# Power.net
KiCad netlist of a schematic drawn in Altium Designer
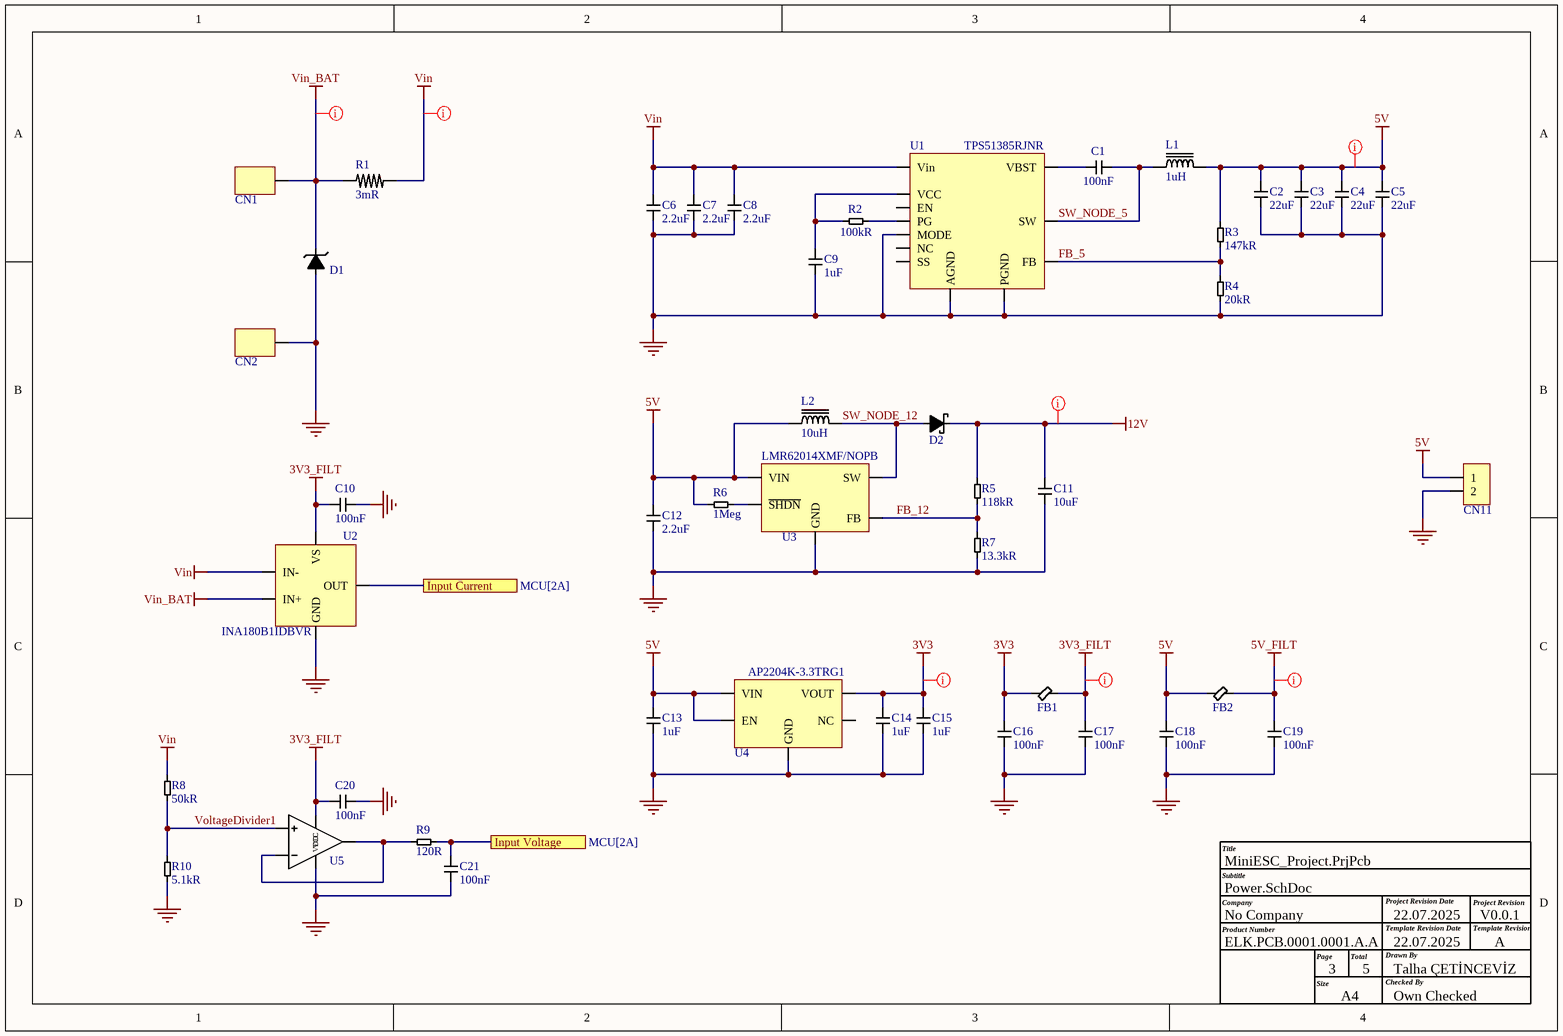
[diagram p0: Power.SchDoc]

(export (version "E")
  (design (tool "Eeschema 10.0.6"))
  (components
    (comp (ref "C1")
      (value "100nF")
      (footprint "CAP 0805")
      (description "50V 100nF X7R ±10% 0805 Multilayer Ceramic Capacitors MLCC - SMD/SMT ROHS")
      (fields
        (field (name "MANUFACTURER") "Samsung")
        (field (name "MANUFACTURER PART NUMBER") "CL21B104KBCNNNC")
      )
      (libsource (lib "ESC_Int") (part "CL21B104KBCNNNC"))
    )
    (comp (ref "C2")
      (value "22uF")
      (footprint "CAP 1206")
      (description "Multilayer Ceramic Capacitor, 22 uF, 10 V, ± 10%, X7R, 1206 [3216 Metric]")
      (fields
        (field (name "MANUFACTURER") "Samsung")
        (field (name "MANUFACTURER PART NUMBER") "CL31B226KPHNNNE")
      )
      (libsource (lib "ESC_Int") (part "CL31B226KPHNNNE"))
    )
    (comp (ref "C3")
      (value "22uF")
      (footprint "CAP 1206")
      (description "Multilayer Ceramic Capacitor, 22 uF, 10 V, ± 10%, X7R, 1206 [3216 Metric]")
      (fields
        (field (name "MANUFACTURER") "Samsung")
        (field (name "MANUFACTURER PART NUMBER") "CL31B226KPHNNNE")
      )
      (libsource (lib "ESC_Int") (part "CL31B226KPHNNNE"))
    )
    (comp (ref "C4")
      (value "22uF")
      (footprint "CAP 1206")
      (description "Multilayer Ceramic Capacitor, 22 uF, 10 V, ± 10%, X7R, 1206 [3216 Metric]")
      (fields
        (field (name "MANUFACTURER") "Samsung")
        (field (name "MANUFACTURER PART NUMBER") "CL31B226KPHNNNE")
      )
      (libsource (lib "ESC_Int") (part "CL31B226KPHNNNE"))
    )
    (comp (ref "C5")
      (value "22uF")
      (footprint "CAP 1206")
      (description "Multilayer Ceramic Capacitor, 22 uF, 10 V, ± 10%, X7R, 1206 [3216 Metric]")
      (fields
        (field (name "MANUFACTURER") "Samsung")
        (field (name "MANUFACTURER PART NUMBER") "CL31B226KPHNNNE")
      )
      (libsource (lib "ESC_Int") (part "CL31B226KPHNNNE"))
    )
    (comp (ref "C6")
      (value "2.2uF")
      (footprint "CAP 1206")
      (description "50V 2.2uF X7R ±10% 1206 Multilayer Ceramic Capacitors MLCC - SMD/SMT ROHS")
      (fields
        (field (name "MANUFACTURER") "Samsung")
        (field (name "MANUFACTURER PART NUMBER") "CL31B225KBHNNNE")
      )
      (libsource (lib "ESC_Int") (part "CL31B225KBHNNNE"))
    )
    (comp (ref "C7")
      (value "2.2uF")
      (footprint "CAP 1206")
      (description "50V 2.2uF X7R ±10% 1206 Multilayer Ceramic Capacitors MLCC - SMD/SMT ROHS")
      (fields
        (field (name "MANUFACTURER") "Samsung")
        (field (name "MANUFACTURER PART NUMBER") "CL31B225KBHNNNE")
      )
      (libsource (lib "ESC_Int") (part "CL31B225KBHNNNE"))
    )
    (comp (ref "C8")
      (value "2.2uF")
      (footprint "CAP 1206")
      (description "50V 2.2uF X7R ±10% 1206 Multilayer Ceramic Capacitors MLCC - SMD/SMT ROHS")
      (fields
        (field (name "MANUFACTURER") "Samsung")
        (field (name "MANUFACTURER PART NUMBER") "CL31B225KBHNNNE")
      )
      (libsource (lib "ESC_Int") (part "CL31B225KBHNNNE"))
    )
    (comp (ref "C9")
      (value "1uF")
      (footprint "CAP 0805")
      (description "Ceramic Capacitor, Ceramic, 50V, 10% +Tol, 10% -Tol, X7R, 15% TC, 1uF, Surface Mount, 0805")
      (fields
        (field (name "MANUFACTURER") "Yageo")
        (field (name "MANUFACTURER PART NUMBER") "CC0805KKX7R9BB105")
      )
      (libsource (lib "ESC_Int") (part "CC0805KKX7R9BB105"))
    )
    (comp (ref "C10")
      (value "100nF")
      (footprint "CAP 0603")
      (description "Multilayer Ceramic Capacitor, CC Series, 0.1 - F, - 10%, X7R, 50 V, 0603 [1608 Metric]")
      (fields
        (field (name "MANUFACTURER") "Yageo")
        (field (name "MANUFACTURER PART NUMBER") "CC0603KRX7R9BB104")
      )
      (libsource (lib "ESC_Int") (part "CC0603KRX7R9BB104"))
    )
    (comp (ref "C11")
      (value "10uF")
      (footprint "CAP 0805")
      (description "25V 10uF X5R ±10% 0805 Multilayer Ceramic Capacitors MLCC - SMD/SMT ROHS")
      (fields
        (field (name "MANUFACTURER") "Samsung")
        (field (name "MANUFACTURER PART NUMBER") "CL21A106KAYNNNE")
      )
      (libsource (lib "ESC_Int") (part "CL21A106KAYNNNE"))
    )
    (comp (ref "C12")
      (value "2.2uF")
      (footprint "CAP 1206")
      (description "50V 2.2uF X7R ±10% 1206 Multilayer Ceramic Capacitors MLCC - SMD/SMT ROHS")
      (fields
        (field (name "MANUFACTURER") "Samsung")
        (field (name "MANUFACTURER PART NUMBER") "CL31B225KBHNNNE")
      )
      (libsource (lib "ESC_Int") (part "CL31B225KBHNNNE"))
    )
    (comp (ref "C13")
      (value "1uF")
      (footprint "CAP 1206")
      (description "Cap Ceramic 1uF 16V X7R 10% SMD 1206 125°C Embossed T/R")
      (fields
        (field (name "MANUFACTURER") "Samsung")
        (field (name "MANUFACTURER PART NUMBER") "CL31B105KOFNNNE")
      )
      (libsource (lib "ESC_Int") (part "CL31B105KOFNNNE"))
    )
    (comp (ref "C14")
      (value "1uF")
      (footprint "CAP 1206")
      (description "Cap Ceramic 1uF 16V X7R 10% SMD 1206 125°C Embossed T/R")
      (fields
        (field (name "MANUFACTURER") "Samsung")
        (field (name "MANUFACTURER PART NUMBER") "CL31B105KOFNNNE")
      )
      (libsource (lib "ESC_Int") (part "CL31B105KOFNNNE"))
    )
    (comp (ref "C15")
      (value "1uF")
      (footprint "CAP 1206")
      (description "Cap Ceramic 1uF 16V X7R 10% SMD 1206 125°C Embossed T/R")
      (fields
        (field (name "MANUFACTURER") "Samsung")
        (field (name "MANUFACTURER PART NUMBER") "CL31B105KOFNNNE")
      )
      (libsource (lib "ESC_Int") (part "CL31B105KOFNNNE"))
    )
    (comp (ref "C16")
      (value "100nF")
      (footprint "CAP 0603")
      (description "Multilayer Ceramic Capacitor, CC Series, 0.1 - F, - 10%, X7R, 50 V, 0603 [1608 Metric]")
      (fields
        (field (name "MANUFACTURER") "Yageo")
        (field (name "MANUFACTURER PART NUMBER") "CC0603KRX7R9BB104")
      )
      (libsource (lib "ESC_Int") (part "CC0603KRX7R9BB104"))
    )
    (comp (ref "C17")
      (value "100nF")
      (footprint "CAP 0603")
      (description "Multilayer Ceramic Capacitor, CC Series, 0.1 - F, - 10%, X7R, 50 V, 0603 [1608 Metric]")
      (fields
        (field (name "MANUFACTURER") "Yageo")
        (field (name "MANUFACTURER PART NUMBER") "CC0603KRX7R9BB104")
      )
      (libsource (lib "ESC_Int") (part "CC0603KRX7R9BB104"))
    )
    (comp (ref "C18")
      (value "100nF")
      (footprint "CAP 0603")
      (description "Multilayer Ceramic Capacitor, CC Series, 0.1 - F, - 10%, X7R, 50 V, 0603 [1608 Metric]")
      (fields
        (field (name "MANUFACTURER") "Yageo")
        (field (name "MANUFACTURER PART NUMBER") "CC0603KRX7R9BB104")
      )
      (libsource (lib "ESC_Int") (part "CC0603KRX7R9BB104"))
    )
    (comp (ref "C19")
      (value "100nF")
      (footprint "CAP 0603")
      (description "Multilayer Ceramic Capacitor, CC Series, 0.1 - F, - 10%, X7R, 50 V, 0603 [1608 Metric]")
      (fields
        (field (name "MANUFACTURER") "Yageo")
        (field (name "MANUFACTURER PART NUMBER") "CC0603KRX7R9BB104")
      )
      (libsource (lib "ESC_Int") (part "CC0603KRX7R9BB104"))
    )
    (comp (ref "C20")
      (value "100nF")
      (footprint "CAP 0603")
      (description "Multilayer Ceramic Capacitor, CC Series, 0.1 - F, - 10%, X7R, 50 V, 0603 [1608 Metric]")
      (fields
        (field (name "MANUFACTURER") "Yageo")
        (field (name "MANUFACTURER PART NUMBER") "CC0603KRX7R9BB104")
      )
      (libsource (lib "ESC_Int") (part "CC0603KRX7R9BB104"))
    )
    (comp (ref "C21")
      (value "100nF")
      (footprint "CAP 0603")
      (description "Multilayer Ceramic Capacitor, CC Series, 0.1 - F, - 10%, X7R, 50 V, 0603 [1608 Metric]")
      (fields
        (field (name "MANUFACTURER") "Yageo")
        (field (name "MANUFACTURER PART NUMBER") "CC0603KRX7R9BB104")
      )
      (libsource (lib "ESC_Int") (part "CC0603KRX7R9BB104"))
    )
    (comp (ref "CN1")
      (value "SMD PAD 1")
      (footprint "SMD PAD 1")
      (libsource (lib "ESC_Int") (part "SMD PAD 1"))
    )
    (comp (ref "CN2")
      (value "SMD PAD 1")
      (footprint "SMD PAD 1")
      (libsource (lib "ESC_Int") (part "SMD PAD 1"))
    )
    (comp (ref "CN11")
      (value "2 Pin SMD")
      (footprint "2 Pin SMD")
      (libsource (lib "ESC_Int") (part "2 Pin SMD"))
    )
    (comp (ref "D1")
      (value "SMAJ33CA-HT")
      (footprint "SMA")
      (description "DIODE TVS 400W 33V DO214AC SMA")
      (fields
        (field (name "MANUFACTURER") "Taiwan Semiconductor")
        (field (name "MANUFACTURER PART NUMBER") "SMAJ33CAH")
      )
      (libsource (lib "ESC_Int") (part "SMAJ33CA-HT"))
    )
    (comp (ref "D2")
      (value "SL02-GS08")
      (footprint "DO-219AB")
      (description "Rectifier Diode Schottky 20V 1.1A 10ns Automotive 2-Pin SMF T/R")
      (fields (field (name "MANUFACTURER") "Vishay"))
      (libsource (lib "ESC_Int") (part "SL02-GS08"))
    )
    (comp (ref "FB1")
      (value "BLM18EG601SN1D")
      (footprint "FB 0603")
      (description "Ferrite Beads Multi-Layer 600Ohm 25% 100MHz 500mA 350mOhm DCR 0603 Paper T/R")
      (fields (field (name "MANUFACTURER") "Murata") (field (name "TOLERANCE") "25%"))
      (libsource (lib "ESC_Int") (part "BLM18EG601SN1D"))
    )
    (comp (ref "FB2")
      (value "BLM18EG601SN1D")
      (footprint "FB 0603")
      (description "Ferrite Beads Multi-Layer 600Ohm 25% 100MHz 500mA 350mOhm DCR 0603 Paper T/R")
      (fields (field (name "MANUFACTURER") "Murata") (field (name "TOLERANCE") "25%"))
      (libsource (lib "ESC_Int") (part "BLM18EG601SN1D"))
    )
    (comp (ref "L1")
      (value "1uH")
      (footprint "11x10")
      (description "1 µH Shielded Molded Inductor 18 A 3.3mOhm Max Nonstandard")
      (fields
        (field (name "MANUFACTURER") "Laird")
        (field (name "MANUFACTURER PART NUMBER") "MGAH10041R0M-10")
      )
      (libsource (lib "ESC_Int") (part "MGAH10041R0M-10"))
    )
    (comp (ref "L2")
      (value "10uH")
      (footprint "3.9x3.9")
      (description "Power inductor, shielded, 20/30% tol, SMT, RoHS, lead-free, halogen-free")
      (fields
        (field (name "MANUFACTURER") "Coilcraft")
        (field (name "MANUFACTURER PART NUMBER") "LPS4018-103MRC")
      )
      (libsource (lib "ESC_Int") (part "LPS4018-103MRC"))
    )
    (comp (ref "R1")
      (value "3mR")
      (footprint "3920")
      (description "RES.SHUNT 3920 3m Ohms 1% 5W AUTO ALUCHROM SMT")
      (fields
        (field (name "MANUFACTURER") "Isabellenhütte")
        (field (name "MANUFACTURER PART NUMBER") "BVS-A-R003-1.0")
      )
      (libsource (lib "ESC_Int") (part "BVS-A-R003-1.0"))
    )
    (comp (ref "R2")
      (value "100kR")
      (footprint "RES 0603")
      (description "100Mw Thick Film Resistors 100Ppm/ 1% 100K 0603 Chip Resistor Surface Mount Rohs")
      (fields
        (field (name "MANUFACTURER") "Yageo")
        (field (name "MANUFACTURER PART NUMBER") "RC0603FR-07100KL")
      )
      (libsource (lib "ESC_Int") (part "RC0603FR-07100KL"))
    )
    (comp (ref "R3")
      (value "147kR")
      (footprint "RES 0603")
      (description "RES.(1608) 0603 147K Ohms 1% 1/10W-S 100PPM")
      (fields
        (field (name "MANUFACTURER") "Multicomp")
        (field (name "MANUFACTURER PART NUMBER") "MC0603SAF1473T5E")
      )
      (libsource (lib "ESC_Int") (part "0603SAF1473T5E"))
    )
    (comp (ref "R4")
      (value "20kR")
      (footprint "RES 0603")
      (description "RES.(1608) 0603 20K Ohms 1% 1/10W-S 100PPM")
      (fields
        (field (name "MANUFACTURER") "Royal Electronic Factory")
        (field (name "MANUFACTURER PART NUMBER") "0603SAF2002T5E")
      )
      (libsource (lib "ESC_Int") (part "0603SAF2002T5E"))
    )
    (comp (ref "R5")
      (value "118kR")
      (footprint "RES 0603")
      (description "Resistor, Thick Film, 118 Kohm, 100MW, 1%")
      (fields
        (field (name "MANUFACTURER") "Multicomp")
        (field (name "MANUFACTURER PART NUMBER") "MC0603SAF1183T5E")
      )
      (libsource (lib "ESC_Int") (part "0603SAF1183T5E"))
    )
    (comp (ref "R6")
      (value "1Meg")
      (footprint "RES 0603")
      (description "Res Thick Film 0603 1M Ohm 5% 0.1W(1/10W) ±200ppm/°C Pad SMD T/R")
      (fields
        (field (name "MANUFACTURER") "Royal Electronic Factory")
        (field (name "MANUFACTURER PART NUMBER") "0603SAJ0105T5E")
      )
      (libsource (lib "ESC_Int") (part "0603SAJ0105T5E"))
    )
    (comp (ref "R7")
      (value "13.3kR")
      (footprint "RES 0603")
      (description "SMD Chip Resistor, 13.3 kohm, ï¿½ 1%, 100 mW, 0603 [1608 Metric], Thick Film, General Purpose")
      (fields
        (field (name "MANUFACTURER") "Yageo")
        (field (name "MANUFACTURER PART NUMBER") "RC0603FR-0713K3L")
      )
      (libsource (lib "ESC_Int") (part "RC0603FR-0713K3L"))
    )
    (comp (ref "R8")
      (value "50kR")
      (footprint "RES 0805")
      (description "RES.(2012) 0805 50K Ohms 1% 1/8W-S 100PPM")
      (fields
        (field (name "MANUFACTURER") "ROYALOHM")
        (field (name "MANUFACTURER PART NUMBER") "0805S8F5002T5E")
      )
      (libsource (lib "ESC_Int") (part "0805S8F5002T5E"))
    )
    (comp (ref "R9")
      (value "120R")
      (footprint "RES 0603")
      (description "RES.(1608) 0603 120 Ohms 1% 1/10W-S 100PPM")
      (fields
        (field (name "MANUFACTURER") "ROYALOHM")
        (field (name "MANUFACTURER PART NUMBER") "0603SAF1200T5E")
      )
      (libsource (lib "ESC_Int") (part "0603SAF1200T5E"))
    )
    (comp (ref "R10")
      (value "5.1kR")
      (footprint "RES 0603")
      (description "Fixed Resistor, Metal Glaze/thick Film, 0.1W, 5100ohm, 50V, 1% +/-Tol, 0603")
      (fields
        (field (name "MANUFACTURER") "Royal Electronic Factory")
        (field (name "MANUFACTURER PART NUMBER") "0603SAF5101T5E")
      )
      (libsource (lib "ESC_Int") (part "0603SAF5101T5E"))
    )
    (comp (ref "U1")
      (value "TPS51385RJNR")
      (footprint "PWQFN-12")
      (fields (field (name "MANUFACTURER") "Texas Instruments"))
      (libsource (lib "ESC_Int") (part "TPS51385RJNR"))
    )
    (comp (ref "U2")
      (value "INA180B1IDBVR")
      (footprint "SOT23-5")
      (description "26V, 350kHz current sense amplifier 5-SOT-23 -40 to 125")
      (fields (field (name "MANUFACTURER") "Texas Instruments"))
      (libsource (lib "ESC_Int") (part "INA180B1IDBVR"))
    )
    (comp (ref "U3")
      (value "LMR62014XMF/NOPB")
      (footprint "SOT23-5")
      (description "SIMPLE SWITCHER® 2.7V to 14V, 1.4A Step-Up Regulator in SOT-23 Package 5-SOT-23 -40 to 125")
      (fields (field (name "MANUFACTURER") "TI National Semiconductor"))
      (libsource (lib "ESC_Int") (part "LMR62014XMF/NOPB"))
    )
    (comp (ref "U4")
      (value "AP2204K-3.3TRG1")
      (footprint "SOT23-5")
      (description "Linear Voltage Regulator IC Positive Fixed 1 Output 3.3V 150mA SOT-23-5")
      (fields (field (name "MANUFACTURER") "Diodes"))
      (libsource (lib "ESC_Int") (part "AP2204K-3.3TRG1"))
    )
    (comp (ref "U5")
      (value "LMV321ILT")
      (footprint "SOT23-5")
      (description "LMV321 Series 6 V 1 MHz Low Power Rail to Rail Operational Amplifier - SOT-23-5")
      (fields (field (name "MANUFACTURER") "STMicroelectronics"))
      (libsource (lib "ESC_Int") (part "LMV321ILT"))
    )
  )
  (nets
    (net (code "1") (name "/FB_5") (class "Default")
      (node (ref "R3") (pin "1") (pinfunction "1_1") (pintype "passive"))
      (node (ref "R4") (pin "2") (pinfunction "2_2") (pintype "passive"))
      (node (ref "U1") (pin "4") (pinfunction "FB_4") (pintype "passive"))
    )
    (net (code "2") (name "/FB_12") (class "Default")
      (node (ref "R5") (pin "1") (pinfunction "1_1") (pintype "passive"))
      (node (ref "R7") (pin "2") (pinfunction "2_2") (pintype "passive"))
      (node (ref "U3") (pin "3") (pinfunction "FB_3") (pintype "passive"))
    )
    (net (code "3") (name "/Input Current") (class "Default")
      (node (ref "U2") (pin "1") (pinfunction "OUT_1") (pintype "passive"))
    )
    (net (code "4") (name "/Input Voltage") (class "Default")
      (node (ref "C21") (pin "2") (pinfunction "2_2") (pintype "passive"))
      (node (ref "R9") (pin "2") (pinfunction "2_2") (pintype "passive"))
    )
    (net (code "5") (name "/SW_NODE_5") (class "Default")
      (node (ref "C1") (pin "2") (pinfunction "2_2") (pintype "passive"))
      (node (ref "L1") (pin "1") (pinfunction "1_1") (pintype "passive"))
      (node (ref "U1") (pin "7") (pinfunction "SW_7") (pintype "passive"))
    )
    (net (code "6") (name "/SW_NODE_12") (class "Default")
      (node (ref "D2") (pin "A") (pinfunction "A_A") (pintype "passive"))
      (node (ref "L2") (pin "2") (pinfunction "2_2") (pintype "passive"))
      (node (ref "U3") (pin "1") (pinfunction "SW_1") (pintype "passive"))
    )
    (net (code "7") (name "/VoltageDivider1") (class "Default")
      (node (ref "R10") (pin "2") (pinfunction "2_2") (pintype "passive"))
      (node (ref "R8") (pin "1") (pinfunction "1_1") (pintype "passive"))
      (node (ref "U5") (pin "1") (pinfunction "NON_Inverting_input_1") (pintype "passive"))
    )
    (net (code "8") (name "3V3") (class "Default")
      (node (ref "C14") (pin "2") (pinfunction "2_2") (pintype "passive"))
      (node (ref "C15") (pin "2") (pinfunction "2_2") (pintype "passive"))
      (node (ref "C16") (pin "2") (pinfunction "2_2") (pintype "passive"))
      (node (ref "FB1") (pin "1") (pinfunction "1_1") (pintype "passive"))
      (node (ref "U4") (pin "5") (pinfunction "VOUT_5") (pintype "passive"))
    )
    (net (code "9") (name "3V3_FILT") (class "Default")
      (node (ref "C10") (pin "1") (pinfunction "1_1") (pintype "passive"))
      (node (ref "C17") (pin "2") (pinfunction "2_2") (pintype "passive"))
      (node (ref "C20") (pin "1") (pinfunction "1_1") (pintype "passive"))
      (node (ref "FB1") (pin "2") (pinfunction "2_2") (pintype "passive"))
      (node (ref "U2") (pin "5") (pinfunction "VS_5") (pintype "passive"))
      (node (ref "U5") (pin "5") (pinfunction "VCC_5") (pintype "passive"))
    )
    (net (code "10") (name "5V") (class "Default")
      (node (ref "C12") (pin "2") (pinfunction "2_2") (pintype "passive"))
      (node (ref "C13") (pin "2") (pinfunction "2_2") (pintype "passive"))
      (node (ref "C18") (pin "2") (pinfunction "2_2") (pintype "passive"))
      (node (ref "C2") (pin "2") (pinfunction "2_2") (pintype "passive"))
      (node (ref "C3") (pin "2") (pinfunction "2_2") (pintype "passive"))
      (node (ref "C4") (pin "2") (pinfunction "2_2") (pintype "passive"))
      (node (ref "C5") (pin "2") (pinfunction "2_2") (pintype "passive"))
      (node (ref "CN11") (pin "1") (pinfunction "1_1") (pintype "passive"))
      (node (ref "FB2") (pin "1") (pinfunction "1_1") (pintype "passive"))
      (node (ref "L1") (pin "2") (pinfunction "2_2") (pintype "passive"))
      (node (ref "L2") (pin "1") (pinfunction "1_1") (pintype "passive"))
      (node (ref "R3") (pin "2") (pinfunction "2_2") (pintype "passive"))
      (node (ref "R6") (pin "1") (pinfunction "1_1") (pintype "passive"))
      (node (ref "U3") (pin "5") (pinfunction "VIN_5") (pintype "passive"))
      (node (ref "U4") (pin "1") (pinfunction "VIN_1") (pintype "passive"))
      (node (ref "U4") (pin "3") (pinfunction "EN_3") (pintype "passive"))
    )
    (net (code "11") (name "5V_FILT") (class "Default")
      (node (ref "C19") (pin "2") (pinfunction "2_2") (pintype "passive"))
      (node (ref "FB2") (pin "2") (pinfunction "2_2") (pintype "passive"))
    )
    (net (code "12") (name "12V") (class "Default")
      (node (ref "C11") (pin "2") (pinfunction "2_2") (pintype "passive"))
      (node (ref "D2") (pin "C") (pinfunction "C_C") (pintype "passive"))
      (node (ref "R5") (pin "2") (pinfunction "2_2") (pintype "passive"))
    )
    (net (code "13") (name "GND") (class "Default")
      (node (ref "C10") (pin "2") (pinfunction "2_2") (pintype "passive"))
      (node (ref "C11") (pin "1") (pinfunction "3_1") (pintype "passive"))
      (node (ref "C12") (pin "1") (pinfunction "3_1") (pintype "passive"))
      (node (ref "C13") (pin "1") (pinfunction "3_1") (pintype "passive"))
      (node (ref "C14") (pin "1") (pinfunction "3_1") (pintype "passive"))
      (node (ref "C15") (pin "1") (pinfunction "3_1") (pintype "passive"))
      (node (ref "C16") (pin "1") (pinfunction "1_1") (pintype "passive"))
      (node (ref "C17") (pin "1") (pinfunction "1_1") (pintype "passive"))
      (node (ref "C18") (pin "1") (pinfunction "1_1") (pintype "passive"))
      (node (ref "C19") (pin "1") (pinfunction "1_1") (pintype "passive"))
      (node (ref "C2") (pin "1") (pinfunction "3_1") (pintype "passive"))
      (node (ref "C20") (pin "2") (pinfunction "2_2") (pintype "passive"))
      (node (ref "C21") (pin "1") (pinfunction "1_1") (pintype "passive"))
      (node (ref "C3") (pin "1") (pinfunction "3_1") (pintype "passive"))
      (node (ref "C4") (pin "1") (pinfunction "3_1") (pintype "passive"))
      (node (ref "C5") (pin "1") (pinfunction "3_1") (pintype "passive"))
      (node (ref "C6") (pin "1") (pinfunction "3_1") (pintype "passive"))
      (node (ref "C7") (pin "1") (pinfunction "3_1") (pintype "passive"))
      (node (ref "C8") (pin "1") (pinfunction "3_1") (pintype "passive"))
      (node (ref "C9") (pin "1") (pinfunction "1_1") (pintype "passive"))
      (node (ref "CN11") (pin "2") (pinfunction "2_2") (pintype "passive"))
      (node (ref "CN2") (pin "1") (pinfunction "1_1") (pintype "passive"))
      (node (ref "D1") (pin "A") (pinfunction "A_A") (pintype "passive"))
      (node (ref "R10") (pin "1") (pinfunction "1_1") (pintype "passive"))
      (node (ref "R4") (pin "1") (pinfunction "1_1") (pintype "passive"))
      (node (ref "R7") (pin "1") (pinfunction "1_1") (pintype "passive"))
      (node (ref "U1") (pin "10") (pinfunction "AGND_10") (pintype "passive"))
      (node (ref "U1") (pin "12") (pinfunction "MODE_12") (pintype "passive"))
      (node (ref "U1") (pin "2") (pinfunction "PGND_2") (pintype "passive"))
      (node (ref "U2") (pin "2") (pinfunction "GND_2") (pintype "passive"))
      (node (ref "U3") (pin "2") (pinfunction "GND_2") (pintype "passive"))
      (node (ref "U4") (pin "2") (pinfunction "GND_2") (pintype "passive"))
      (node (ref "U5") (pin "2") (pinfunction "VDD_2") (pintype "passive"))
    )
    (net (code "14") (name "Net-(C1-3)") (class "Default")
      (node (ref "C1") (pin "1") (pinfunction "3_1") (pintype "passive"))
      (node (ref "U1") (pin "8") (pinfunction "VBST_8") (pintype "passive"))
    )
    (net (code "15") (name "Net-(U1-PG)") (class "Default")
      (node (ref "R2") (pin "2") (pinfunction "2_2") (pintype "passive"))
      (node (ref "U1") (pin "3") (pinfunction "PG_3") (pintype "passive"))
    )
    (net (code "16") (name "Net-(U1-VCC)") (class "Default")
      (node (ref "C9") (pin "2") (pinfunction "2_2") (pintype "passive"))
      (node (ref "R2") (pin "1") (pinfunction "1_1") (pintype "passive"))
      (node (ref "U1") (pin "9") (pinfunction "VCC_9") (pintype "passive"))
    )
    (net (code "17") (name "Net-(U3-~{SHDN})") (class "Default")
      (node (ref "R6") (pin "2") (pinfunction "2_2") (pintype "passive"))
      (node (ref "U3") (pin "4") (pinfunction "~{SHDN}_4") (pintype "passive"))
    )
    (net (code "18") (name "Net-(U5-Inverting_Input)") (class "Default")
      (node (ref "R9") (pin "1") (pinfunction "1_1") (pintype "passive"))
      (node (ref "U5") (pin "3") (pinfunction "Inverting_Input_3") (pintype "passive"))
      (node (ref "U5") (pin "4") (pinfunction "Output_4") (pintype "passive"))
    )
    (net (code "19") (name "Vin") (class "Default")
      (node (ref "C6") (pin "2") (pinfunction "2_2") (pintype "passive"))
      (node (ref "C7") (pin "2") (pinfunction "2_2") (pintype "passive"))
      (node (ref "C8") (pin "2") (pinfunction "2_2") (pintype "passive"))
      (node (ref "R1") (pin "2") (pinfunction "2_2") (pintype "passive"))
      (node (ref "R8") (pin "2") (pinfunction "2_2") (pintype "passive"))
      (node (ref "U1") (pin "1") (pinfunction "Vin_1") (pintype "passive"))
      (node (ref "U2") (pin "4") (pinfunction "IN-_4") (pintype "passive"))
    )
    (net (code "20") (name "Vin_BAT") (class "Default")
      (node (ref "CN1") (pin "1") (pinfunction "1_1") (pintype "passive"))
      (node (ref "D1") (pin "C") (pinfunction "C_C") (pintype "passive"))
      (node (ref "R1") (pin "1") (pinfunction "1_1") (pintype "passive"))
      (node (ref "U2") (pin "3") (pinfunction "IN+_3") (pintype "passive"))
    )
    (net (code "21") (name "unconnected-(U1-EN-Pad11)") (class "Default")
      (node (ref "U1") (pin "11") (pinfunction "EN_11") (pintype "passive"))
    )
    (net (code "22") (name "unconnected-(U1-NC-Pad6)") (class "Default")
      (node (ref "U1") (pin "6") (pinfunction "NC_6") (pintype "passive"))
    )
    (net (code "23") (name "unconnected-(U1-SS-Pad5)") (class "Default")
      (node (ref "U1") (pin "5") (pinfunction "SS_5") (pintype "passive"))
    )
    (net (code "24") (name "unconnected-(U4-NC-Pad4)") (class "Default")
      (node (ref "U4") (pin "4") (pinfunction "NC_4") (pintype "passive"))
    )
  )
)
